# STM32F103RBT6.net
KiCad netlist of a schematic drawn in Altium Designer
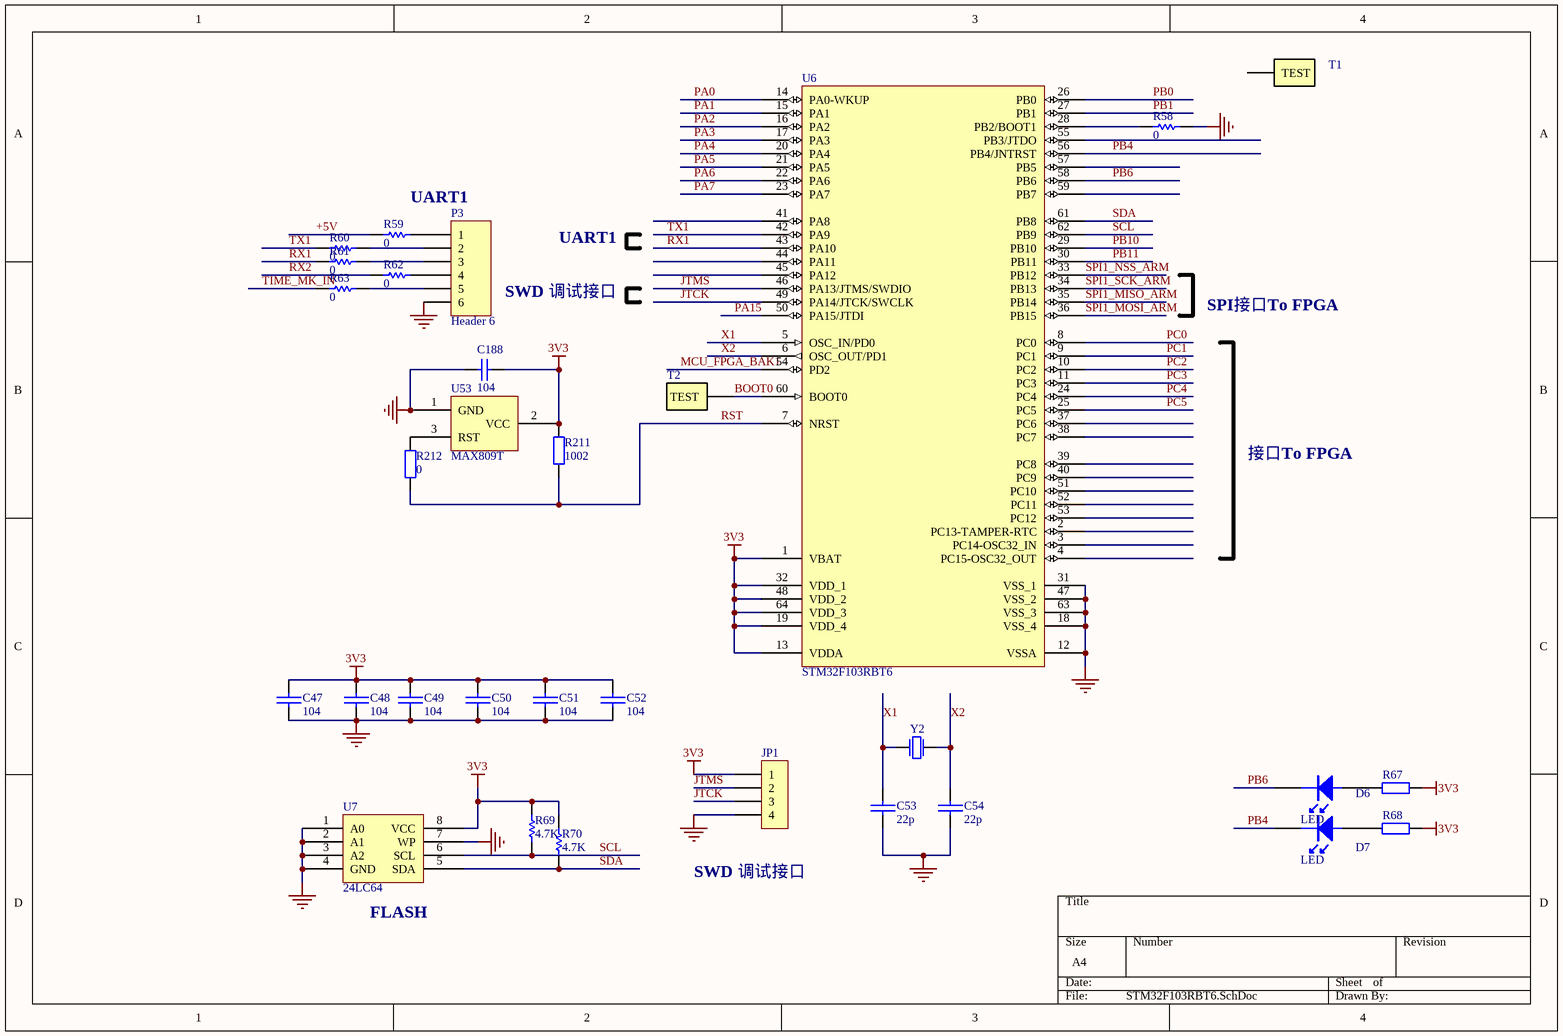
[diagram p0: STM32F103RBT6.SchDoc]

(export (version "E")
  (design (tool "Eeschema 10.0.6"))
  (components
    (comp (ref "C47")
      (value "104")
      (footprint "0805C")
      (description "Capacitor")
      (libsource (lib "*") (part "CAP"))
    )
    (comp (ref "C48")
      (value "104")
      (footprint "0805C")
      (description "Capacitor")
      (libsource (lib "*") (part "CAP"))
    )
    (comp (ref "C49")
      (value "104")
      (footprint "0805C")
      (description "Capacitor")
      (libsource (lib "*") (part "CAP"))
    )
    (comp (ref "C50")
      (value "104")
      (footprint "0805C")
      (description "Capacitor")
      (libsource (lib "*") (part "CAP"))
    )
    (comp (ref "C51")
      (value "104")
      (footprint "0805C")
      (description "Capacitor")
      (libsource (lib "*") (part "CAP"))
    )
    (comp (ref "C52")
      (value "104")
      (footprint "0805C")
      (description "Capacitor")
      (libsource (lib "*") (part "CAP"))
    )
    (comp (ref "C53")
      (value "22p")
      (footprint "0805C")
      (description "Capacitor")
      (libsource (lib "*") (part "CAP"))
    )
    (comp (ref "C54")
      (value "22p")
      (footprint "0805C")
      (description "Capacitor")
      (libsource (lib "*") (part "CAP"))
    )
    (comp (ref "C188")
      (value "104")
      (footprint "0805C")
      (description "Capacitor")
      (fields (field (name "PUBLISHER") "Altium Limited"))
      (libsource (lib "Miscellaneous Devices") (part "Cap"))
    )
    (comp (ref "D6") (value "LED") (footprint "0805_LED") (libsource (lib "*") (part "LED")))
    (comp (ref "D7") (value "LED") (footprint "0805_LED") (libsource (lib "*") (part "LED")))
    (comp (ref "JP1")
      (value "~")
      (footprint "HDR1X4")
      (description "Connector")
      (libsource (lib "*") (part "CON4"))
    )
    (comp (ref "P3")
      (value "Header 6")
      (footprint "HDR1X6")
      (description "Header, 6-Pin")
      (fields (field (name "PUBLISHER") "Altium Limited"))
      (libsource (lib "Miscellaneous Connectors") (part "Header 6"))
    )
    (comp (ref "R58")
      (value "0")
      (footprint "0805R")
      (description "Resistor")
      (fields (field (name "PUBLISHER") "*"))
      (libsource (lib "*") (part "Res1"))
    )
    (comp (ref "R59")
      (value "0")
      (footprint "0805R")
      (description "Resistor")
      (fields (field (name "PUBLISHER") "*"))
      (libsource (lib "*") (part "Res1"))
    )
    (comp (ref "R60")
      (value "0")
      (footprint "0805R")
      (description "Resistor")
      (fields (field (name "PUBLISHER") "*"))
      (libsource (lib "*") (part "Res1"))
    )
    (comp (ref "R61")
      (value "0")
      (footprint "0805R")
      (description "Resistor")
      (fields (field (name "PUBLISHER") "*"))
      (libsource (lib "*") (part "Res1"))
    )
    (comp (ref "R62")
      (value "0")
      (footprint "0805R")
      (description "Resistor")
      (fields (field (name "PUBLISHER") "*"))
      (libsource (lib "*") (part "Res1"))
    )
    (comp (ref "R63")
      (value "0")
      (footprint "0805R")
      (description "Resistor")
      (fields (field (name "PUBLISHER") "*"))
      (libsource (lib "*") (part "Res1"))
    )
    (comp (ref "R67")
      (value "4701")
      (footprint "0805R")
      (description "Resistor")
      (fields (field (name "PUBLISHER") "Altium Limited"))
      (libsource (lib "Miscellaneous Devices") (part "Res2"))
    )
    (comp (ref "R68")
      (value "4701")
      (footprint "0805R")
      (description "Resistor")
      (fields (field (name "PUBLISHER") "Altium Limited"))
      (libsource (lib "Miscellaneous Devices") (part "Res2"))
    )
    (comp (ref "R69")
      (value "4.7K")
      (footprint "0805R")
      (description "Resistor")
      (fields (field (name "PUBLISHER") "*"))
      (libsource (lib "*") (part "Res1"))
    )
    (comp (ref "R70")
      (value "4.7K")
      (footprint "0805R")
      (description "Resistor")
      (fields (field (name "PUBLISHER") "*"))
      (libsource (lib "*") (part "Res1"))
    )
    (comp (ref "R211")
      (value "1002")
      (footprint "0805R")
      (description "Resistor")
      (fields (field (name "PUBLISHER") "Altium Limited"))
      (libsource (lib "") (part "Res2_1"))
    )
    (comp (ref "R212")
      (value "0")
      (footprint "0805R")
      (description "Resistor")
      (fields (field (name "PUBLISHER") "Altium Limited"))
      (libsource (lib "") (part "Res2_1"))
    )
    (comp (ref "T1") (value "~") (footprint "TEST") (libsource (lib "USB30_Project") (part "TEST")))
    (comp (ref "T2") (value "~") (footprint "TEST") (libsource (lib "") (part "TEST_1")))
    (comp (ref "U6")
      (value "STM32F103RBT6")
      (footprint "LQFP64_M")
      (description "STM32 ARM-based 32-bit MCU with 128 Kbytes Flash, 64-pin LQFP, Industrial Temperature")
      (fields (field (name "PUBLISHER") "*"))
      (libsource (lib "*") (part "STM32F103RBT6"))
    )
    (comp (ref "U7") (value "24LC64") (footprint "SO8") (libsource (lib "*") (part "24C02")))
    (comp (ref "U53")
      (value "MAX809T")
      (footprint "MAX809-SOT23")
      (libsource (lib "Schlib1") (part "MAX809T"))
    )
    (comp (ref "Y2")
      (value "~")
      (footprint "XTAL_8M")
      (description "Crystal Oscillator")
      (libsource (lib "*") (part "XTAL"))
    )
  )
  (nets
    (net (code "1") (name "/+5V") (class "Default")
      (node (ref "R59") (pin "1") (pinfunction "1_1") (pintype "passive"))
    )
    (net (code "2") (name "/BOOT0") (class "Default")
      (node (ref "T2") (pin "1") (pinfunction "TEST_1") (pintype "passive"))
      (node (ref "U6") (pin "60") (pinfunction "BOOT0_60") (pintype "input"))
    )
    (net (code "3") (name "/JTCK") (class "Default")
      (node (ref "JP1") (pin "3") (pinfunction "3_3") (pintype "passive"))
      (node (ref "U6") (pin "49") (pinfunction "PA14/JTCK/SWCLK_49") (pintype "bidirectional"))
    )
    (net (code "4") (name "/JTMS") (class "Default")
      (node (ref "JP1") (pin "2") (pinfunction "2_2") (pintype "passive"))
      (node (ref "U6") (pin "46") (pinfunction "PA13/JTMS/SWDIO_46") (pintype "bidirectional"))
    )
    (net (code "5") (name "/MCU_FPGA_BAK1") (class "Default")
      (node (ref "U6") (pin "54") (pinfunction "PD2_54") (pintype "bidirectional"))
    )
    (net (code "6") (name "/PA0") (class "Default")
      (node (ref "U6") (pin "14") (pinfunction "PA0-WKUP_14") (pintype "bidirectional"))
    )
    (net (code "7") (name "/PA1") (class "Default")
      (node (ref "U6") (pin "15") (pinfunction "PA1_15") (pintype "bidirectional"))
    )
    (net (code "8") (name "/PA2") (class "Default")
      (node (ref "U6") (pin "16") (pinfunction "PA2_16") (pintype "bidirectional"))
    )
    (net (code "9") (name "/PA3") (class "Default")
      (node (ref "U6") (pin "17") (pinfunction "PA3_17") (pintype "bidirectional"))
    )
    (net (code "10") (name "/PA4") (class "Default")
      (node (ref "U6") (pin "20") (pinfunction "PA4_20") (pintype "bidirectional"))
    )
    (net (code "11") (name "/PA5") (class "Default")
      (node (ref "U6") (pin "21") (pinfunction "PA5_21") (pintype "bidirectional"))
    )
    (net (code "12") (name "/PA6") (class "Default")
      (node (ref "U6") (pin "22") (pinfunction "PA6_22") (pintype "bidirectional"))
    )
    (net (code "13") (name "/PA7") (class "Default")
      (node (ref "U6") (pin "23") (pinfunction "PA7_23") (pintype "bidirectional"))
    )
    (net (code "14") (name "/PA15") (class "Default")
      (node (ref "U6") (pin "50") (pinfunction "PA15/JTDI_50") (pintype "bidirectional"))
    )
    (net (code "15") (name "/PB0") (class "Default")
      (node (ref "U6") (pin "26") (pinfunction "PB0_26") (pintype "bidirectional"))
    )
    (net (code "16") (name "/PB1") (class "Default")
      (node (ref "U6") (pin "27") (pinfunction "PB1_27") (pintype "bidirectional"))
    )
    (net (code "17") (name "/PB4") (class "Default")
      (node (ref "D7") (pin "2") (pinfunction "K_2") (pintype "passive"))
      (node (ref "U6") (pin "56") (pinfunction "PB4/JNTRST_56") (pintype "bidirectional"))
    )
    (net (code "18") (name "/PB6") (class "Default")
      (node (ref "D6") (pin "2") (pinfunction "K_2") (pintype "passive"))
      (node (ref "U6") (pin "58") (pinfunction "PB6_58") (pintype "bidirectional"))
    )
    (net (code "19") (name "/PB10") (class "Default")
      (node (ref "U6") (pin "29") (pinfunction "PB10_29") (pintype "bidirectional"))
    )
    (net (code "20") (name "/PB11") (class "Default")
      (node (ref "U6") (pin "30") (pinfunction "PB11_30") (pintype "bidirectional"))
    )
    (net (code "21") (name "/PC0") (class "Default")
      (node (ref "U6") (pin "8") (pinfunction "PC0_8") (pintype "bidirectional"))
    )
    (net (code "22") (name "/PC1") (class "Default")
      (node (ref "U6") (pin "9") (pinfunction "PC1_9") (pintype "bidirectional"))
    )
    (net (code "23") (name "/PC2") (class "Default")
      (node (ref "U6") (pin "10") (pinfunction "PC2_10") (pintype "bidirectional"))
    )
    (net (code "24") (name "/PC3") (class "Default")
      (node (ref "U6") (pin "11") (pinfunction "PC3_11") (pintype "bidirectional"))
    )
    (net (code "25") (name "/PC4") (class "Default")
      (node (ref "U6") (pin "24") (pinfunction "PC4_24") (pintype "bidirectional"))
    )
    (net (code "26") (name "/PC5") (class "Default")
      (node (ref "U6") (pin "25") (pinfunction "PC5_25") (pintype "bidirectional"))
    )
    (net (code "27") (name "/RST") (class "Default")
      (node (ref "R211") (pin "2") (pinfunction "2_2") (pintype "passive"))
      (node (ref "R212") (pin "2") (pinfunction "2_2") (pintype "passive"))
      (node (ref "U6") (pin "7") (pinfunction "NRST_7") (pintype "bidirectional"))
    )
    (net (code "28") (name "/RX1") (class "Default")
      (node (ref "R61") (pin "1") (pinfunction "1_1") (pintype "passive"))
      (node (ref "U6") (pin "43") (pinfunction "PA10_43") (pintype "bidirectional"))
    )
    (net (code "29") (name "/RX2") (class "Default")
      (node (ref "R62") (pin "1") (pinfunction "1_1") (pintype "passive"))
    )
    (net (code "30") (name "/SCL") (class "Default")
      (node (ref "R69") (pin "1") (pinfunction "1_1") (pintype "passive"))
      (node (ref "U6") (pin "62") (pinfunction "PB9_62") (pintype "bidirectional"))
      (node (ref "U7") (pin "6") (pinfunction "SCL_6") (pintype "passive"))
    )
    (net (code "31") (name "/SDA") (class "Default")
      (node (ref "R70") (pin "1") (pinfunction "1_1") (pintype "passive"))
      (node (ref "U6") (pin "61") (pinfunction "PB8_61") (pintype "bidirectional"))
      (node (ref "U7") (pin "5") (pinfunction "SDA_5") (pintype "passive"))
    )
    (net (code "32") (name "/SPI1_MISO_ARM") (class "Default")
      (node (ref "U6") (pin "35") (pinfunction "PB14_35") (pintype "bidirectional"))
    )
    (net (code "33") (name "/SPI1_MOSI_ARM") (class "Default")
      (node (ref "U6") (pin "36") (pinfunction "PB15_36") (pintype "bidirectional"))
    )
    (net (code "34") (name "/SPI1_NSS_ARM") (class "Default")
      (node (ref "U6") (pin "33") (pinfunction "PB12_33") (pintype "bidirectional"))
    )
    (net (code "35") (name "/SPI1_SCK_ARM") (class "Default")
      (node (ref "U6") (pin "34") (pinfunction "PB13_34") (pintype "bidirectional"))
    )
    (net (code "36") (name "/TIME_MK_IN") (class "Default")
      (node (ref "R63") (pin "1") (pinfunction "1_1") (pintype "passive"))
    )
    (net (code "37") (name "/TX1") (class "Default")
      (node (ref "R60") (pin "1") (pinfunction "1_1") (pintype "passive"))
      (node (ref "U6") (pin "42") (pinfunction "PA9_42") (pintype "bidirectional"))
    )
    (net (code "38") (name "/X1") (class "Default")
      (node (ref "C53") (pin "1") (pinfunction "1_1") (pintype "passive"))
      (node (ref "U6") (pin "5") (pinfunction "OSC_IN/PD0_5") (pintype "input"))
      (node (ref "Y2") (pin "2") (pinfunction "P2_2") (pintype "passive"))
    )
    (net (code "39") (name "/X2") (class "Default")
      (node (ref "C54") (pin "1") (pinfunction "1_1") (pintype "passive"))
      (node (ref "U6") (pin "6") (pinfunction "OSC_OUT/PD1_6") (pintype "output"))
      (node (ref "Y2") (pin "1") (pinfunction "P1_1") (pintype "passive"))
    )
    (net (code "40") (name "3V3") (class "Default")
      (node (ref "C188") (pin "1") (pinfunction "1_1") (pintype "passive"))
      (node (ref "C47") (pin "1") (pinfunction "1_1") (pintype "passive"))
      (node (ref "C48") (pin "1") (pinfunction "1_1") (pintype "passive"))
      (node (ref "C49") (pin "1") (pinfunction "1_1") (pintype "passive"))
      (node (ref "C50") (pin "1") (pinfunction "1_1") (pintype "passive"))
      (node (ref "C51") (pin "1") (pinfunction "1_1") (pintype "passive"))
      (node (ref "C52") (pin "1") (pinfunction "1_1") (pintype "passive"))
      (node (ref "JP1") (pin "1") (pinfunction "1_1") (pintype "passive"))
      (node (ref "R211") (pin "1") (pinfunction "1_1") (pintype "passive"))
      (node (ref "R67") (pin "2") (pinfunction "2_2") (pintype "passive"))
      (node (ref "R68") (pin "2") (pinfunction "2_2") (pintype "passive"))
      (node (ref "R69") (pin "2") (pinfunction "2_2") (pintype "passive"))
      (node (ref "R70") (pin "2") (pinfunction "2_2") (pintype "passive"))
      (node (ref "U53") (pin "2") (pinfunction "VCC_2") (pintype "passive"))
      (node (ref "U6") (pin "1") (pinfunction "VBAT_1") (pintype "power_in"))
      (node (ref "U6") (pin "13") (pinfunction "VDDA_13") (pintype "power_in"))
      (node (ref "U6") (pin "19") (pinfunction "VDD_4_19") (pintype "power_in"))
      (node (ref "U6") (pin "32") (pinfunction "VDD_1_32") (pintype "power_in"))
      (node (ref "U6") (pin "48") (pinfunction "VDD_2_48") (pintype "power_in"))
      (node (ref "U6") (pin "64") (pinfunction "VDD_3_64") (pintype "power_in"))
      (node (ref "U7") (pin "8") (pinfunction "VCC_8") (pintype "passive"))
    )
    (net (code "41") (name "GND") (class "Default")
      (node (ref "C188") (pin "2") (pinfunction "2_2") (pintype "passive"))
      (node (ref "C47") (pin "2") (pinfunction "2_2") (pintype "passive"))
      (node (ref "C48") (pin "2") (pinfunction "2_2") (pintype "passive"))
      (node (ref "C49") (pin "2") (pinfunction "2_2") (pintype "passive"))
      (node (ref "C50") (pin "2") (pinfunction "2_2") (pintype "passive"))
      (node (ref "C51") (pin "2") (pinfunction "2_2") (pintype "passive"))
      (node (ref "C52") (pin "2") (pinfunction "2_2") (pintype "passive"))
      (node (ref "C53") (pin "2") (pinfunction "2_2") (pintype "passive"))
      (node (ref "C54") (pin "2") (pinfunction "2_2") (pintype "passive"))
      (node (ref "JP1") (pin "4") (pinfunction "4_4") (pintype "passive"))
      (node (ref "P3") (pin "6") (pinfunction "6_6") (pintype "passive"))
      (node (ref "R58") (pin "2") (pinfunction "2_2") (pintype "passive"))
      (node (ref "U53") (pin "1") (pinfunction "GND_1") (pintype "passive"))
      (node (ref "U6") (pin "12") (pinfunction "VSSA_12") (pintype "power_in"))
      (node (ref "U6") (pin "18") (pinfunction "VSS_4_18") (pintype "power_in"))
      (node (ref "U6") (pin "31") (pinfunction "VSS_1_31") (pintype "power_in"))
      (node (ref "U6") (pin "47") (pinfunction "VSS_2_47") (pintype "power_in"))
      (node (ref "U6") (pin "63") (pinfunction "VSS_3_63") (pintype "power_in"))
      (node (ref "U7") (pin "1") (pinfunction "A0_1") (pintype "passive"))
      (node (ref "U7") (pin "2") (pinfunction "A1_2") (pintype "passive"))
      (node (ref "U7") (pin "3") (pinfunction "A2_3") (pintype "passive"))
      (node (ref "U7") (pin "4") (pinfunction "GND_4") (pintype "passive"))
      (node (ref "U7") (pin "7") (pinfunction "WP_7") (pintype "passive"))
    )
    (net (code "42") (name "Net-(D6-A)") (class "Default")
      (node (ref "D6") (pin "1") (pinfunction "A_1") (pintype "passive"))
      (node (ref "R67") (pin "1") (pinfunction "1_1") (pintype "passive"))
    )
    (net (code "43") (name "Net-(D7-A)") (class "Default")
      (node (ref "D7") (pin "1") (pinfunction "A_1") (pintype "passive"))
      (node (ref "R68") (pin "1") (pinfunction "1_1") (pintype "passive"))
    )
    (net (code "44") (name "Net-(P3-Pad1)") (class "Default")
      (node (ref "P3") (pin "1") (pinfunction "1_1") (pintype "passive"))
      (node (ref "R59") (pin "2") (pinfunction "2_2") (pintype "passive"))
    )
    (net (code "45") (name "Net-(P3-Pad2)") (class "Default")
      (node (ref "P3") (pin "2") (pinfunction "2_2") (pintype "passive"))
      (node (ref "R60") (pin "2") (pinfunction "2_2") (pintype "passive"))
    )
    (net (code "46") (name "Net-(P3-Pad3)") (class "Default")
      (node (ref "P3") (pin "3") (pinfunction "3_3") (pintype "passive"))
      (node (ref "R61") (pin "2") (pinfunction "2_2") (pintype "passive"))
    )
    (net (code "47") (name "Net-(P3-Pad4)") (class "Default")
      (node (ref "P3") (pin "4") (pinfunction "4_4") (pintype "passive"))
      (node (ref "R62") (pin "2") (pinfunction "2_2") (pintype "passive"))
    )
    (net (code "48") (name "Net-(P3-Pad5)") (class "Default")
      (node (ref "P3") (pin "5") (pinfunction "5_5") (pintype "passive"))
      (node (ref "R63") (pin "2") (pinfunction "2_2") (pintype "passive"))
    )
    (net (code "49") (name "Net-(U6-PB2{slash}BOOT1)") (class "Default")
      (node (ref "R58") (pin "1") (pinfunction "1_1") (pintype "passive"))
      (node (ref "U6") (pin "28") (pinfunction "PB2/BOOT1_28") (pintype "bidirectional"))
    )
    (net (code "50") (name "Net-(U53-RST)") (class "Default")
      (node (ref "R212") (pin "1") (pinfunction "1_1") (pintype "passive"))
      (node (ref "U53") (pin "3") (pinfunction "RST_3") (pintype "passive"))
    )
    (net (code "51") (name "unconnected-(T1-TEST-Pad1)") (class "Default")
      (node (ref "T1") (pin "1") (pinfunction "TEST_1") (pintype "passive"))
    )
    (net (code "52") (name "unconnected-(U6-PA8-Pad41)") (class "Default")
      (node (ref "U6") (pin "41") (pinfunction "PA8_41") (pintype "bidirectional"))
    )
    (net (code "53") (name "unconnected-(U6-PA11-Pad44)") (class "Default")
      (node (ref "U6") (pin "44") (pinfunction "PA11_44") (pintype "bidirectional"))
    )
    (net (code "54") (name "unconnected-(U6-PA12-Pad45)") (class "Default")
      (node (ref "U6") (pin "45") (pinfunction "PA12_45") (pintype "bidirectional"))
    )
    (net (code "55") (name "unconnected-(U6-PB3{slash}JTDO-Pad55)") (class "Default")
      (node (ref "U6") (pin "55") (pinfunction "PB3/JTDO_55") (pintype "bidirectional"))
    )
    (net (code "56") (name "unconnected-(U6-PB5-Pad57)") (class "Default")
      (node (ref "U6") (pin "57") (pinfunction "PB5_57") (pintype "bidirectional"))
    )
    (net (code "57") (name "unconnected-(U6-PB7-Pad59)") (class "Default")
      (node (ref "U6") (pin "59") (pinfunction "PB7_59") (pintype "bidirectional"))
    )
    (net (code "58") (name "unconnected-(U6-PC6-Pad37)") (class "Default")
      (node (ref "U6") (pin "37") (pinfunction "PC6_37") (pintype "bidirectional"))
    )
    (net (code "59") (name "unconnected-(U6-PC7-Pad38)") (class "Default")
      (node (ref "U6") (pin "38") (pinfunction "PC7_38") (pintype "bidirectional"))
    )
    (net (code "60") (name "unconnected-(U6-PC8-Pad39)") (class "Default")
      (node (ref "U6") (pin "39") (pinfunction "PC8_39") (pintype "bidirectional"))
    )
    (net (code "61") (name "unconnected-(U6-PC9-Pad40)") (class "Default")
      (node (ref "U6") (pin "40") (pinfunction "PC9_40") (pintype "bidirectional"))
    )
    (net (code "62") (name "unconnected-(U6-PC10-Pad51)") (class "Default")
      (node (ref "U6") (pin "51") (pinfunction "PC10_51") (pintype "bidirectional"))
    )
    (net (code "63") (name "unconnected-(U6-PC11-Pad52)") (class "Default")
      (node (ref "U6") (pin "52") (pinfunction "PC11_52") (pintype "bidirectional"))
    )
    (net (code "64") (name "unconnected-(U6-PC12-Pad53)") (class "Default")
      (node (ref "U6") (pin "53") (pinfunction "PC12_53") (pintype "bidirectional"))
    )
    (net (code "65") (name "unconnected-(U6-PC13-TAMPER-RTC-Pad2)") (class "Default")
      (node (ref "U6") (pin "2") (pinfunction "PC13-TAMPER-RTC_2") (pintype "bidirectional"))
    )
    (net (code "66") (name "unconnected-(U6-PC14-OSC32_IN-Pad3)") (class "Default")
      (node (ref "U6") (pin "3") (pinfunction "PC14-OSC32_IN_3") (pintype "bidirectional"))
    )
    (net (code "67") (name "unconnected-(U6-PC15-OSC32_OUT-Pad4)") (class "Default")
      (node (ref "U6") (pin "4") (pinfunction "PC15-OSC32_OUT_4") (pintype "bidirectional"))
    )
  )
)
